# Purr_Cat_Schm.net
KiCad netlist of a schematic drawn in EasyEDA
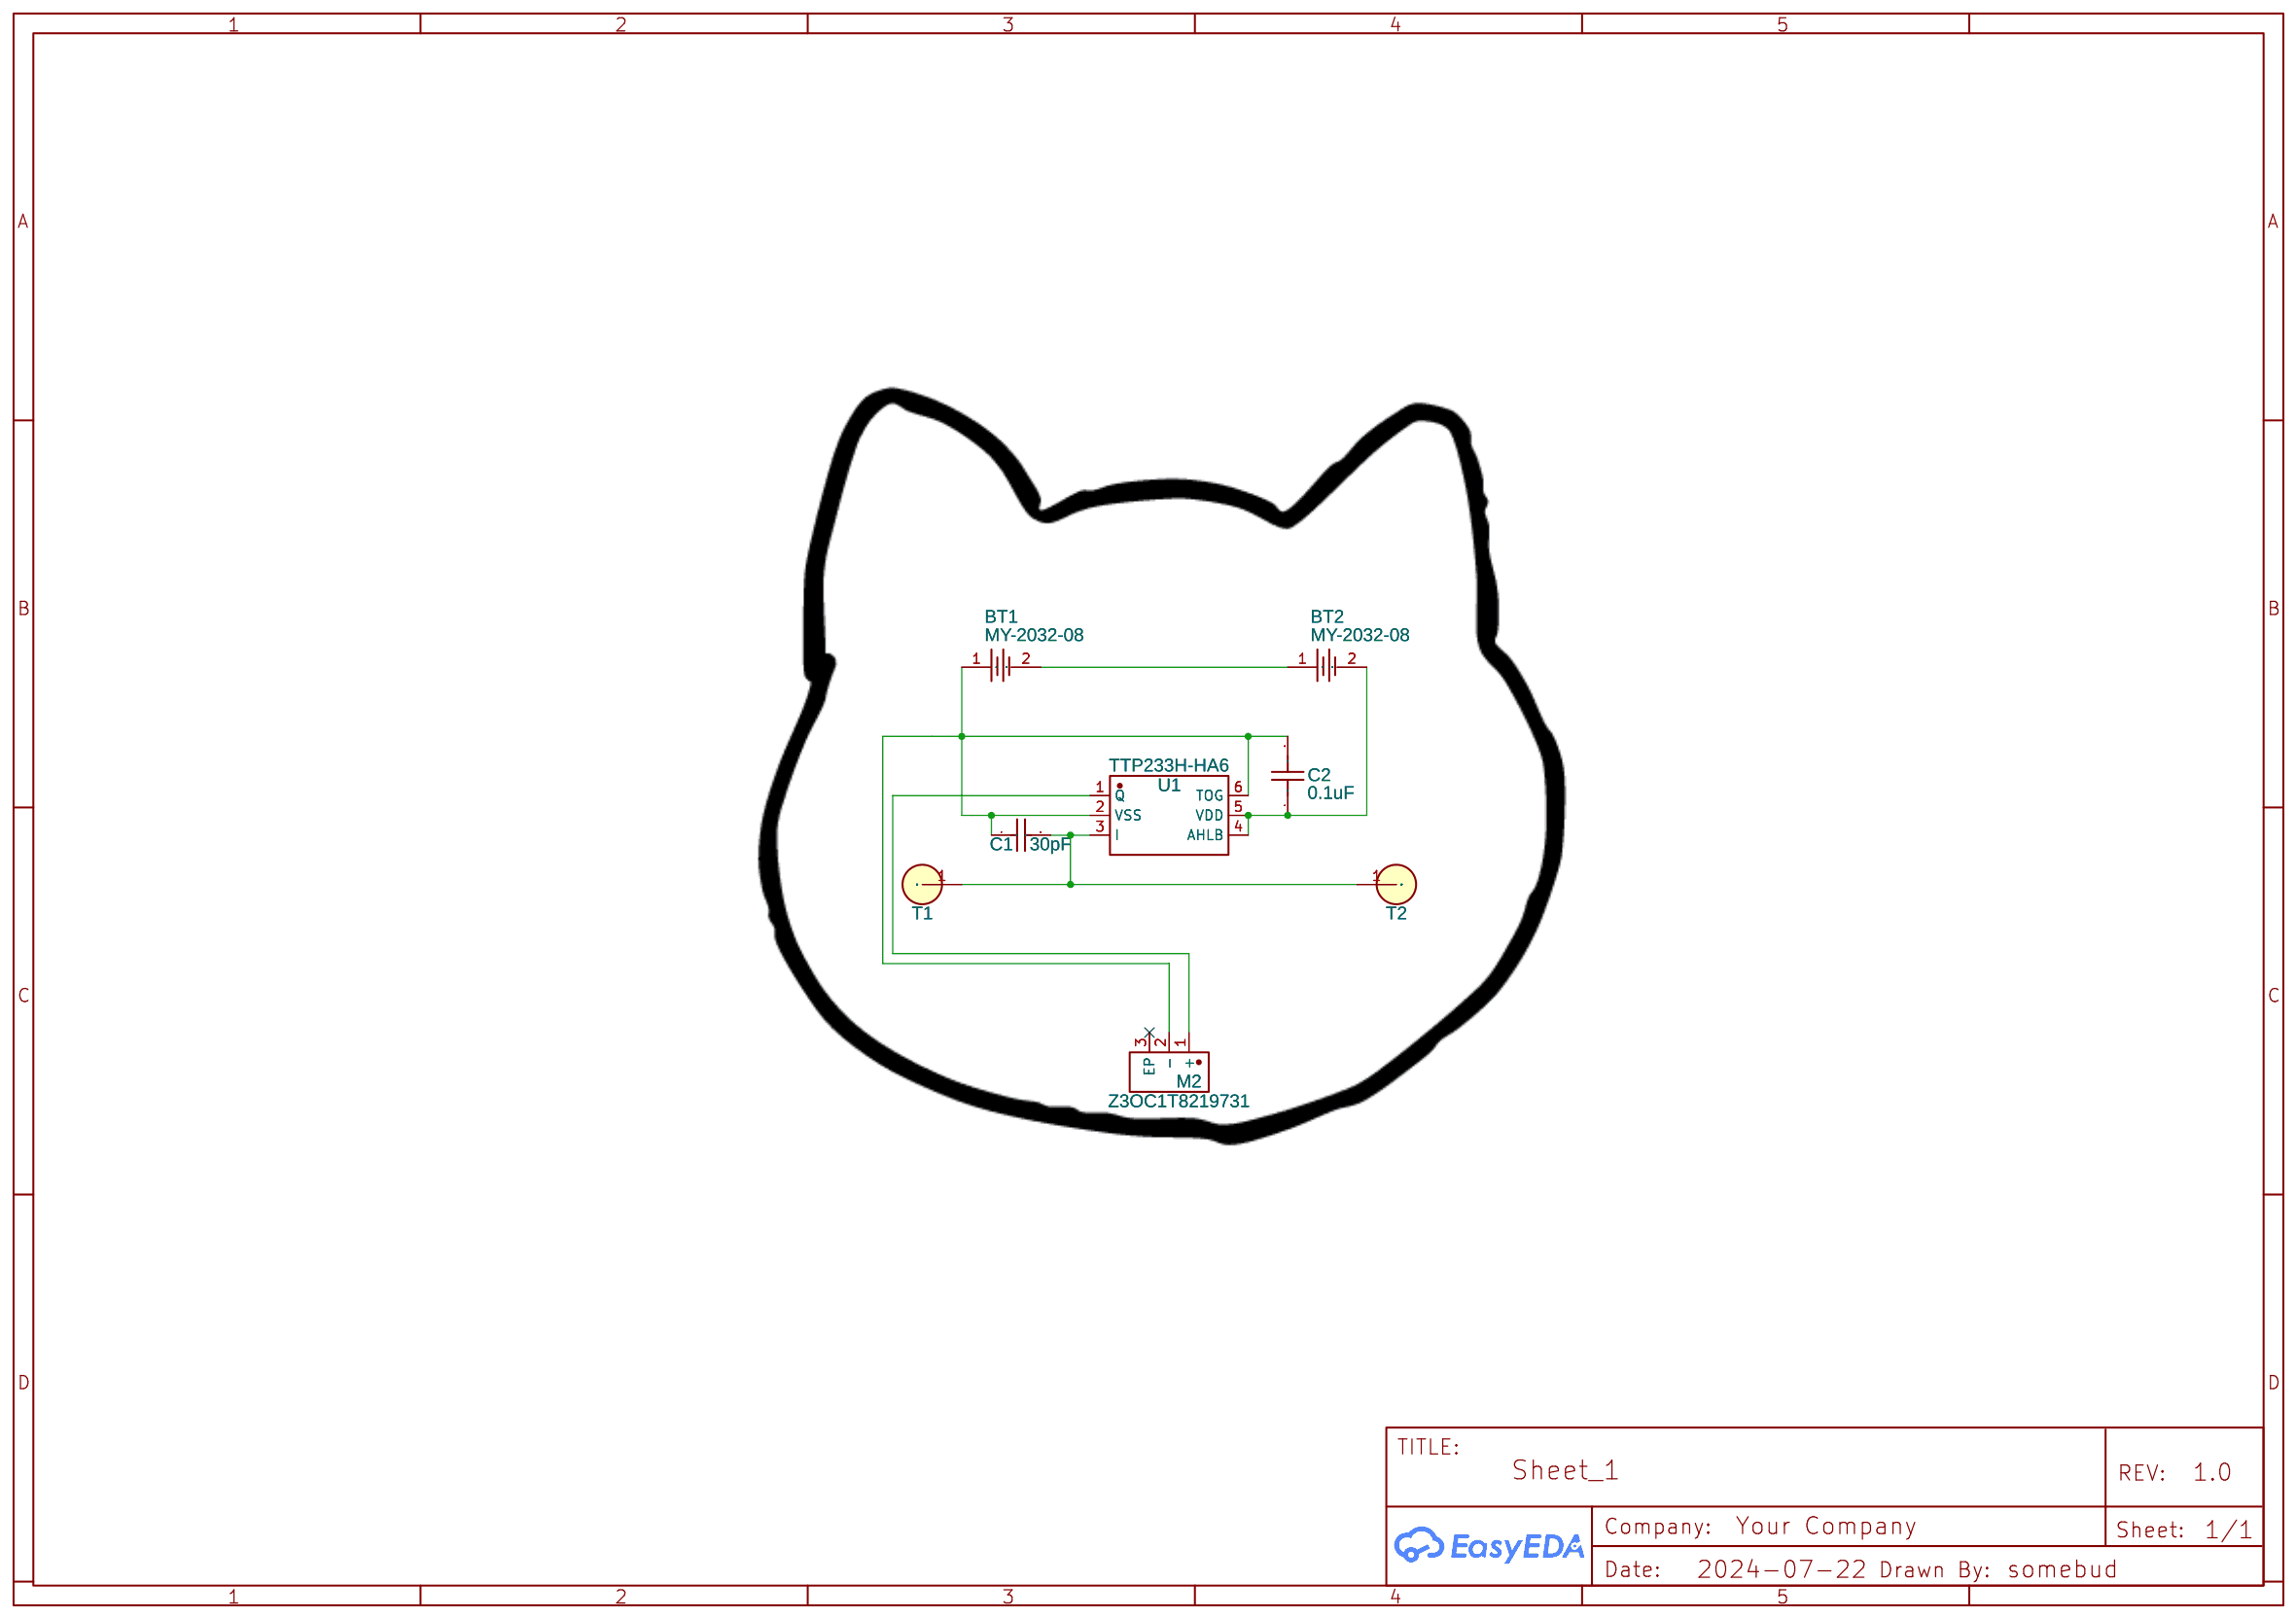
[diagram p0: schematic sheet]

(export (version "E")
  (design (tool "Eeschema 10.0.6"))
  (components
    (comp (ref "BT1")
      (value "MY-2032-08")
      (fields (field (name "Manufacturer") "MYOUNG(美阳)"))
      (libsource (lib "") (part "MY-2032-08"))
    )
    (comp (ref "BT2")
      (value "MY-2032-08")
      (fields (field (name "Manufacturer") "MYOUNG(美阳)"))
      (libsource (lib "") (part "MY-2032-08"))
    )
    (comp (ref "C1")
      (value "30pF")
      (fields (field (name "Manufacturer Part") "0603CG300J500NT") (field (name "Manufacturer") "FH(风华)"))
      (libsource (lib "") (part "0603CG300J500NT"))
    )
    (comp (ref "C2") (value "0.1uF") (libsource (lib "") (part "C_0603_US")))
    (comp (ref "M2")
      (value "Z3OC1T8219731")
      (fields (field (name "Manufacturer") "KOTL(金龙机电)"))
      (libsource (lib "") (part "Z3OC1T8219731"))
    )
    (comp (ref "T1")
      (value "TOUCHPAD 12mm circle nopaste nomask")
      (libsource (lib "") (part "TOUCHPAD 12mm circle nopaste nomask"))
    )
    (comp (ref "T2")
      (value "TOUCHPAD 12mm circle nopaste nomask")
      (libsource (lib "") (part "TOUCHPAD 12mm circle nopaste nomask_1"))
    )
    (comp (ref "U1")
      (value "TTP233H-HA6")
      (fields (field (name "Manufacturer") "TONTEK(通泰)"))
      (libsource (lib "") (part "TTP233H-HA6"))
    )
  )
  (nets
    (net (code "1") (name "Net-(BT1-Pad2)") (class "Default")
      (node (ref "BT1") (pin "2") (pinfunction "2_2") (pintype "input"))
      (node (ref "BT2") (pin "1") (pinfunction "1_1") (pintype "input"))
    )
    (net (code "2") (name "Net-(M2-+)") (class "Default")
      (node (ref "M2") (pin "1") (pinfunction "+_1") (pintype "unspecified"))
      (node (ref "U1") (pin "1") (pinfunction "Q_1") (pintype "unspecified"))
    )
    (net (code "3") (name "Net-(M2--)") (class "Default")
      (node (ref "BT1") (pin "1") (pinfunction "1_1") (pintype "input"))
      (node (ref "C1") (pin "1") (pinfunction "1_1") (pintype "input"))
      (node (ref "C2") (pin "2") (pinfunction "2_2") (pintype "unspecified"))
      (node (ref "M2") (pin "2") (pinfunction "-_2") (pintype "unspecified"))
      (node (ref "U1") (pin "2") (pinfunction "VSS_2") (pintype "unspecified"))
      (node (ref "U1") (pin "6") (pinfunction "TOG_6") (pintype "unspecified"))
    )
    (net (code "4") (name "Net-(T1-Touch)") (class "Default")
      (node (ref "C1") (pin "2") (pinfunction "2_2") (pintype "input"))
      (node (ref "T1") (pin "1") (pinfunction "Touch_1") (pintype "unspecified"))
      (node (ref "T2") (pin "1") (pinfunction "Touch_1") (pintype "unspecified"))
      (node (ref "U1") (pin "3") (pinfunction "I_3") (pintype "unspecified"))
    )
    (net (code "5") (name "Net-(U1-AHLB)") (class "Default")
      (node (ref "BT2") (pin "2") (pinfunction "2_2") (pintype "input"))
      (node (ref "C2") (pin "1") (pinfunction "1_1") (pintype "unspecified"))
      (node (ref "U1") (pin "4") (pinfunction "AHLB_4") (pintype "unspecified"))
      (node (ref "U1") (pin "5") (pinfunction "VDD_5") (pintype "unspecified"))
    )
    (net (code "6") (name "unconnected-(M2-EP-Pad3)") (class "Default")
      (node (ref "M2") (pin "3") (pinfunction "EP_3") (pintype "unspecified+no_connect"))
    )
  )
)
